# Oscillator_RevB.net
KiCad netlist of a schematic drawn in EAGLE
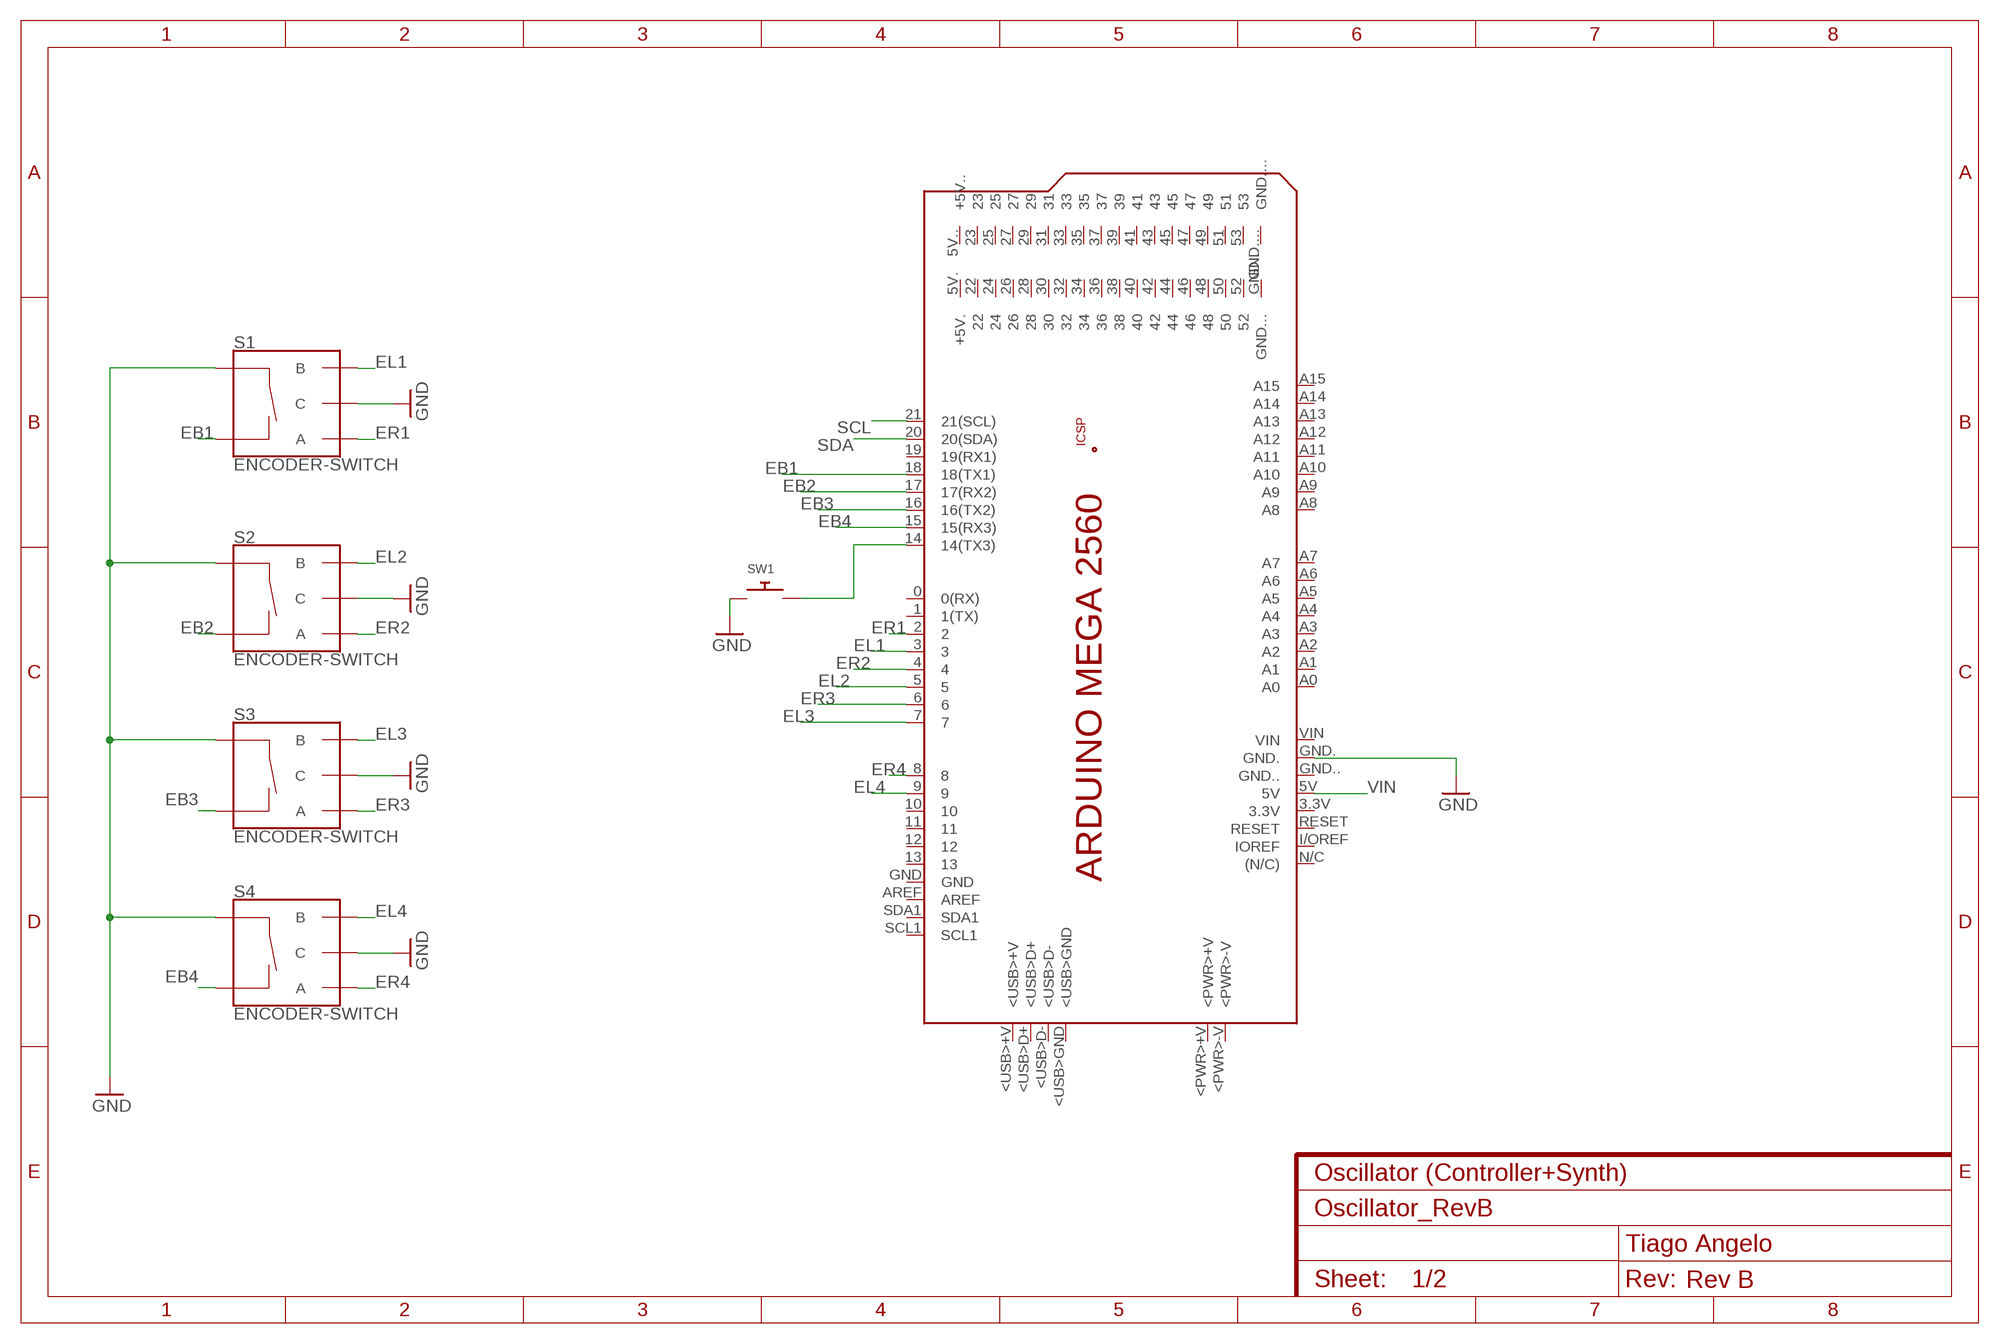
[diagram p0: schematic, sheet 1]
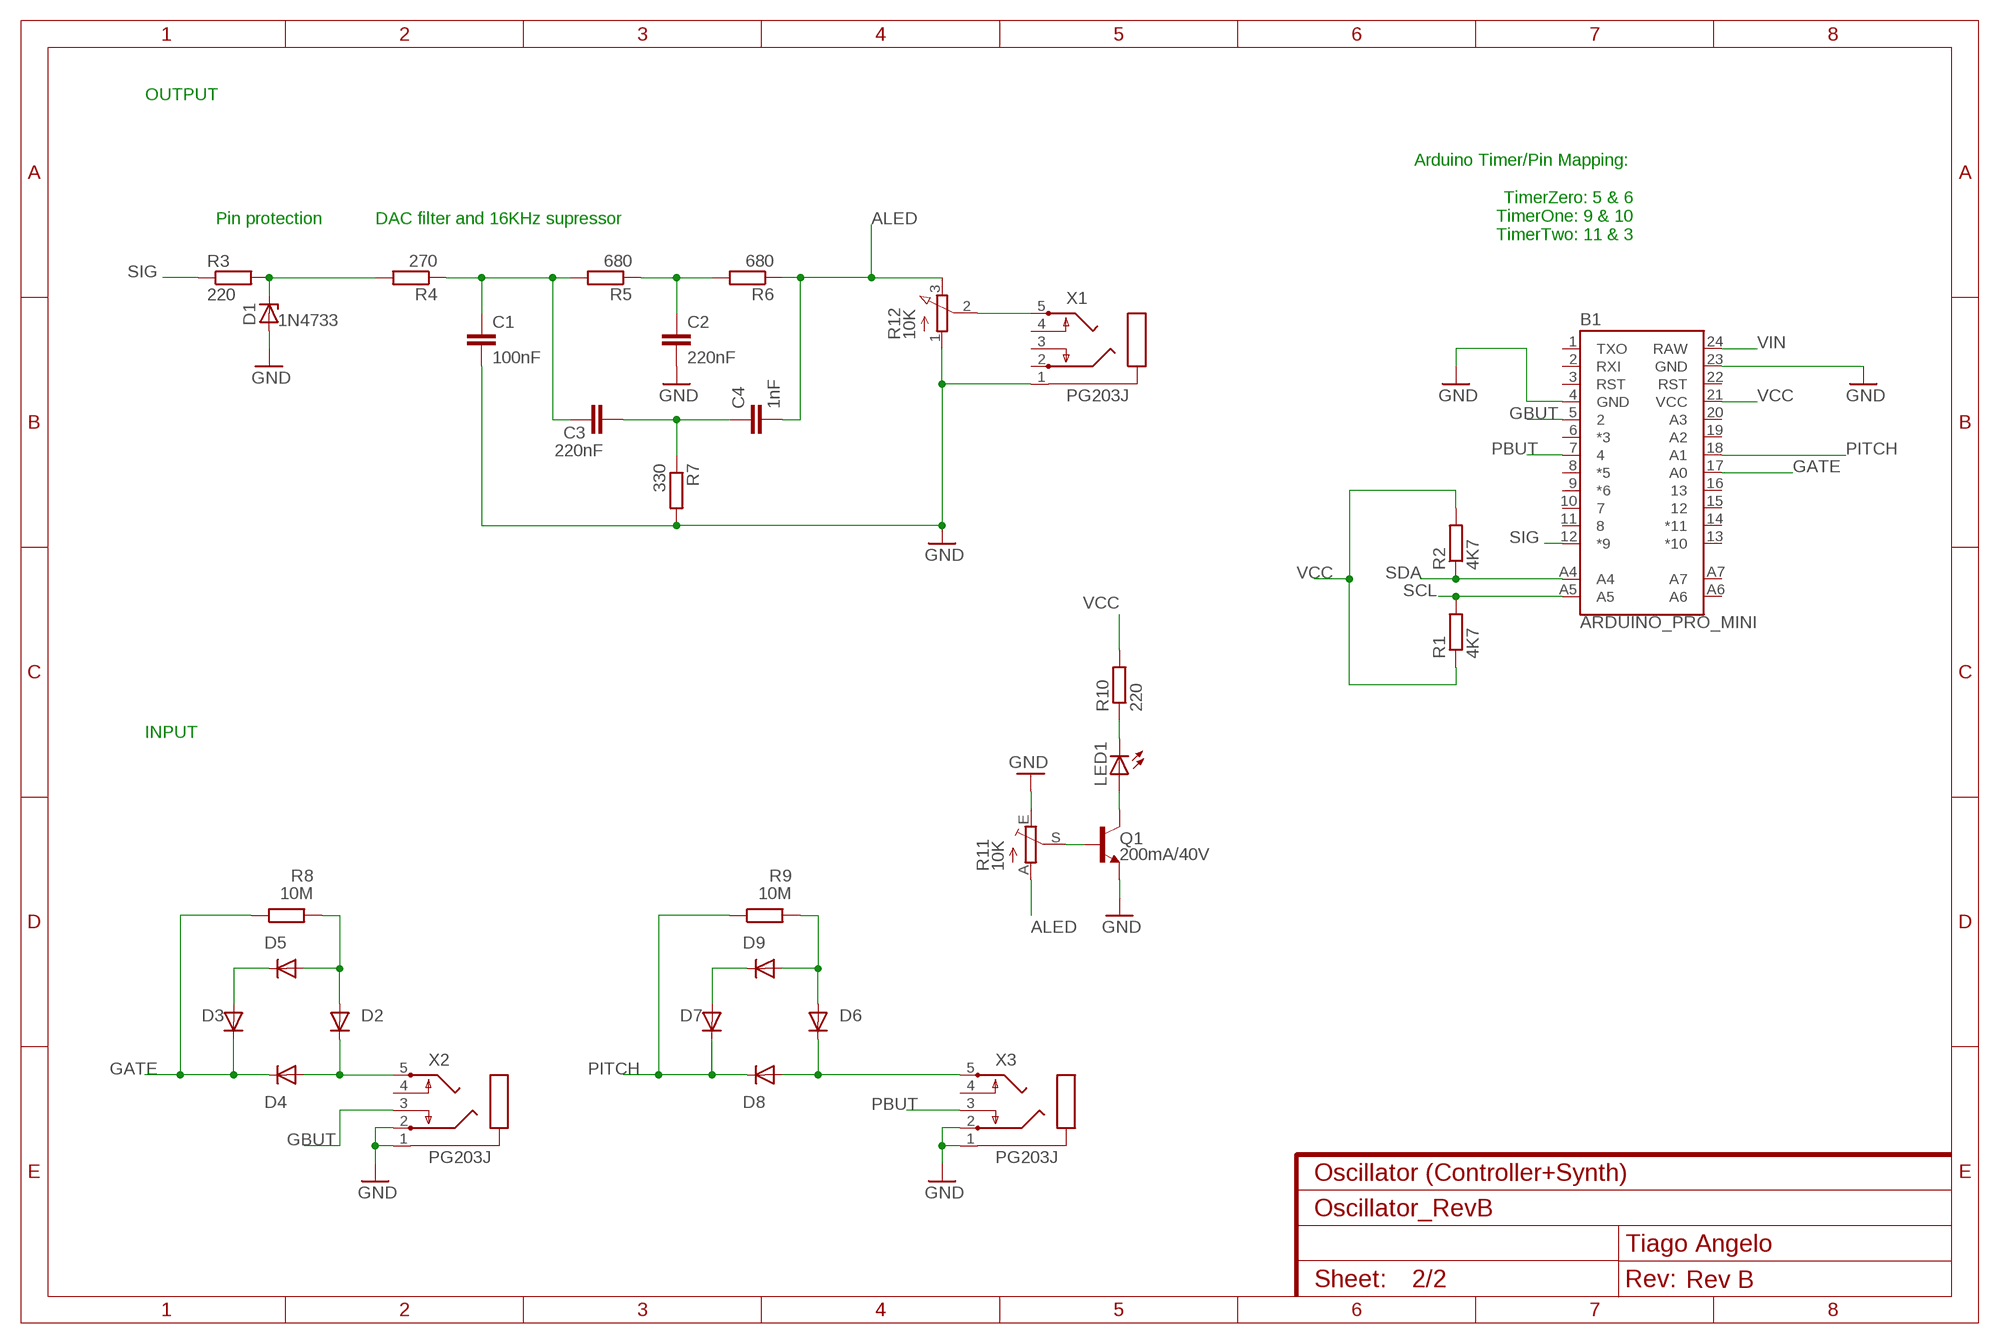
[diagram p1: schematic, sheet 2]

(export (version "E")
  (design (tool "Eeschema 10.0.6"))
  (components
    (comp (ref "B1")
      (value "ARDUINO_PRO_MINI")
      (footprint "eagle-import:ARDUINO_PRO_MINI")
      (libsource (lib "eagle-import") (part "ARDUINO_PRO_MINI"))
    )
    (comp (ref "C1")
      (value "100nF")
      (footprint "eagle-import:C5B3")
      (libsource (lib "eagle-import") (part "C5/3"))
    )
    (comp (ref "C2")
      (value "220nF")
      (footprint "eagle-import:C7.5B6")
      (libsource (lib "eagle-import") (part "C7.5/6"))
    )
    (comp (ref "C3")
      (value "220nF")
      (footprint "eagle-import:C7.5B6")
      (libsource (lib "eagle-import") (part "C7.5/6"))
    )
    (comp (ref "C4")
      (value "1nF")
      (footprint "eagle-import:C5B3")
      (libsource (lib "eagle-import") (part "C5/3"))
    )
    (comp (ref "D1")
      (value "1N4733")
      (footprint "eagle-import:DO34Z7")
      (libsource (lib "eagle-import") (part "ZENER-DIODEDO34-7"))
    )
    (comp (ref "D2")
      (value "1N4004")
      (footprint "eagle-import:DO41-10")
      (libsource (lib "eagle-import") (part "1N4004"))
    )
    (comp (ref "D3")
      (value "1N4004")
      (footprint "eagle-import:DO41-10")
      (libsource (lib "eagle-import") (part "1N4004"))
    )
    (comp (ref "D4")
      (value "1N4004")
      (footprint "eagle-import:DO41-10")
      (libsource (lib "eagle-import") (part "1N4004"))
    )
    (comp (ref "D5")
      (value "1N4004")
      (footprint "eagle-import:DO41-10")
      (libsource (lib "eagle-import") (part "1N4004"))
    )
    (comp (ref "D6")
      (value "1N4004")
      (footprint "eagle-import:DO41-10")
      (libsource (lib "eagle-import") (part "1N4004"))
    )
    (comp (ref "D7")
      (value "1N4004")
      (footprint "eagle-import:DO41-10")
      (libsource (lib "eagle-import") (part "1N4004"))
    )
    (comp (ref "D8")
      (value "1N4004")
      (footprint "eagle-import:DO41-10")
      (libsource (lib "eagle-import") (part "1N4004"))
    )
    (comp (ref "D9")
      (value "1N4004")
      (footprint "eagle-import:DO41-10")
      (libsource (lib "eagle-import") (part "1N4004"))
    )
    (comp (ref "LED1")
      (value "LED5MM")
      (footprint "eagle-import:LED5MM")
      (libsource (lib "eagle-import") (part "LED5MM"))
    )
    (comp (ref "Q1")
      (value "200mA/40V")
      (footprint "eagle-import:TO-92")
      (libsource (lib "eagle-import") (part "TRANS_NPN-2N3904"))
    )
    (comp (ref "R1")
      (value "4K7")
      (footprint "eagle-import:0204_7")
      (libsource (lib "eagle-import") (part "R-EU_0204/7"))
    )
    (comp (ref "R2")
      (value "4K7")
      (footprint "eagle-import:0204_7")
      (libsource (lib "eagle-import") (part "R-EU_0204/7"))
    )
    (comp (ref "R3")
      (value "220")
      (footprint "eagle-import:0204_7")
      (libsource (lib "eagle-import") (part "R-EU_0204/7"))
    )
    (comp (ref "R4")
      (value "270")
      (footprint "eagle-import:0204_7")
      (libsource (lib "eagle-import") (part "R-EU_0204/7"))
    )
    (comp (ref "R5")
      (value "680")
      (footprint "eagle-import:0204_7")
      (libsource (lib "eagle-import") (part "R-EU_0204/7"))
    )
    (comp (ref "R6")
      (value "680")
      (footprint "eagle-import:0204_7")
      (libsource (lib "eagle-import") (part "R-EU_0204/7"))
    )
    (comp (ref "R7")
      (value "330")
      (footprint "eagle-import:0204_7")
      (libsource (lib "eagle-import") (part "R-EU_0204/7"))
    )
    (comp (ref "R8")
      (value "10M")
      (footprint "eagle-import:0204_7")
      (libsource (lib "eagle-import") (part "R-EU_0204/7"))
    )
    (comp (ref "R9")
      (value "10M")
      (footprint "eagle-import:0204_7")
      (libsource (lib "eagle-import") (part "R-EU_0204/7"))
    )
    (comp (ref "R10")
      (value "220")
      (footprint "eagle-import:0204_7")
      (libsource (lib "eagle-import") (part "R-EU_0204/7"))
    )
    (comp (ref "R11")
      (value "10K")
      (footprint "eagle-import:LI10")
      (libsource (lib "eagle-import") (part "TRIM_EU-LI10"))
    )
    (comp (ref "R12")
      (value "10K")
      (footprint "eagle-import:3RP_1610N")
      (libsource (lib "eagle-import") (part "3RP/1610N"))
    )
    (comp (ref "X1")
      (value "PG203J")
      (footprint "eagle-import:PG203J")
      (libsource (lib "eagle-import") (part "PG203J"))
    )
    (comp (ref "X2")
      (value "PG203J")
      (footprint "eagle-import:PG203J")
      (libsource (lib "eagle-import") (part "PG203J"))
    )
    (comp (ref "X3")
      (value "PG203J")
      (footprint "eagle-import:PG203J")
      (libsource (lib "eagle-import") (part "PG203J"))
    )
    (comp (ref "PCB1")
      (value "ARDUINO_MEGA2560")
      (footprint "eagle-import:ARDUINO_MEGA2560")
      (libsource (lib "eagle-import") (part "ARDUINO_MEGA2560"))
    )
    (comp (ref "S1")
      (value "ENCODER-SWITCH")
      (footprint "eagle-import:ROTARY_ENC_PLAIN")
      (libsource (lib "eagle-import") (part "ENCODER-SWITCH"))
    )
    (comp (ref "S2")
      (value "ENCODER-SWITCH")
      (footprint "eagle-import:ROTARY_ENC_PLAIN")
      (libsource (lib "eagle-import") (part "ENCODER-SWITCH"))
    )
    (comp (ref "S3")
      (value "ENCODER-SWITCH")
      (footprint "eagle-import:ROTARY_ENC_PLAIN")
      (libsource (lib "eagle-import") (part "ENCODER-SWITCH"))
    )
    (comp (ref "S4")
      (value "ENCODER-SWITCH")
      (footprint "eagle-import:ROTARY_ENC_PLAIN")
      (libsource (lib "eagle-import") (part "ENCODER-SWITCH"))
    )
    (comp (ref "SW1")
      (value "SWITCH_PUSHBUTTONEVQ-PE")
      (footprint "eagle-import:TACT_PANA-EVQ")
      (libsource (lib "eagle-import") (part "SWITCH_PUSHBUTTONEVQ-PE"))
    )
  )
  (nets
    (net (code "1") (name "ALED") (class "Default")
      (node (ref "C4") (pin "2") (pinfunction "2_2") (pintype "passive"))
      (node (ref "R11") (pin "A") (pinfunction "A_A") (pintype "passive"))
      (node (ref "R12") (pin "3") (pinfunction "E_3") (pintype "passive"))
      (node (ref "R6") (pin "1") (pinfunction "1_1") (pintype "passive"))
    )
    (net (code "2") (name "EB1") (class "Default")
      (node (ref "PCB1") (pin "18") (pinfunction "18(TX1)_18") (pintype "bidirectional"))
      (node (ref "S1") (pin "SW-") (pinfunction "SW-_SW-") (pintype "bidirectional"))
    )
    (net (code "3") (name "EB2") (class "Default")
      (node (ref "PCB1") (pin "17") (pinfunction "17(RX2)_17") (pintype "bidirectional"))
      (node (ref "S2") (pin "SW-") (pinfunction "SW-_SW-") (pintype "bidirectional"))
    )
    (net (code "4") (name "EB3") (class "Default")
      (node (ref "PCB1") (pin "16") (pinfunction "16(TX2)_16") (pintype "bidirectional"))
      (node (ref "S3") (pin "SW-") (pinfunction "SW-_SW-") (pintype "bidirectional"))
    )
    (net (code "5") (name "EB4") (class "Default")
      (node (ref "PCB1") (pin "15") (pinfunction "15(RX3)_15") (pintype "bidirectional"))
      (node (ref "S4") (pin "SW-") (pinfunction "SW-_SW-") (pintype "bidirectional"))
    )
    (net (code "6") (name "EL1") (class "Default")
      (node (ref "PCB1") (pin "3") (pinfunction "3_3") (pintype "bidirectional"))
      (node (ref "S1") (pin "B") (pinfunction "B_B") (pintype "bidirectional"))
    )
    (net (code "7") (name "EL2") (class "Default")
      (node (ref "PCB1") (pin "5") (pinfunction "5_5") (pintype "bidirectional"))
      (node (ref "S2") (pin "B") (pinfunction "B_B") (pintype "bidirectional"))
    )
    (net (code "8") (name "EL3") (class "Default")
      (node (ref "PCB1") (pin "7") (pinfunction "7_7") (pintype "bidirectional"))
      (node (ref "S3") (pin "B") (pinfunction "B_B") (pintype "bidirectional"))
    )
    (net (code "9") (name "EL4") (class "Default")
      (node (ref "PCB1") (pin "9") (pinfunction "9_9") (pintype "bidirectional"))
      (node (ref "S4") (pin "B") (pinfunction "B_B") (pintype "bidirectional"))
    )
    (net (code "10") (name "ER1") (class "Default")
      (node (ref "PCB1") (pin "2") (pinfunction "2_2") (pintype "bidirectional"))
      (node (ref "S1") (pin "A") (pinfunction "A_A") (pintype "bidirectional"))
    )
    (net (code "11") (name "ER2") (class "Default")
      (node (ref "PCB1") (pin "4") (pinfunction "4_4") (pintype "bidirectional"))
      (node (ref "S2") (pin "A") (pinfunction "A_A") (pintype "bidirectional"))
    )
    (net (code "12") (name "ER3") (class "Default")
      (node (ref "PCB1") (pin "6") (pinfunction "6_6") (pintype "bidirectional"))
      (node (ref "S3") (pin "A") (pinfunction "A_A") (pintype "bidirectional"))
    )
    (net (code "13") (name "ER4") (class "Default")
      (node (ref "PCB1") (pin "8") (pinfunction "8_8") (pintype "bidirectional"))
      (node (ref "S4") (pin "A") (pinfunction "A_A") (pintype "bidirectional"))
    )
    (net (code "14") (name "GATE") (class "Default")
      (node (ref "B1") (pin "17") (pinfunction "A0_17") (pintype "bidirectional"))
      (node (ref "D3") (pin "C") (pinfunction "C_C") (pintype "passive"))
      (node (ref "D4") (pin "C") (pinfunction "C_C") (pintype "passive"))
      (node (ref "R8") (pin "1") (pinfunction "1_1") (pintype "passive"))
    )
    (net (code "15") (name "GBUT") (class "Default")
      (node (ref "B1") (pin "5") (pinfunction "2_5") (pintype "bidirectional"))
      (node (ref "X2") (pin "3") (pinfunction "3_3") (pintype "passive"))
    )
    (net (code "16") (name "GND") (class "Default")
      (node (ref "B1") (pin "23") (pinfunction "GND_23") (pintype "power_in"))
      (node (ref "B1") (pin "4") (pinfunction "GND_4") (pintype "power_in"))
      (node (ref "C1") (pin "2") (pinfunction "2_2") (pintype "passive"))
      (node (ref "C2") (pin "2") (pinfunction "2_2") (pintype "passive"))
      (node (ref "D1") (pin "A") (pinfunction "A_A") (pintype "passive"))
      (node (ref "PCB1") (pin "GND.") (pinfunction "GND._GND.") (pintype "bidirectional"))
      (node (ref "Q1") (pin "1") (pinfunction "E_1") (pintype "passive"))
      (node (ref "R11") (pin "E") (pinfunction "E_E") (pintype "passive"))
      (node (ref "R12") (pin "1") (pinfunction "A_1") (pintype "passive"))
      (node (ref "R7") (pin "2") (pinfunction "2_2") (pintype "passive"))
      (node (ref "S1") (pin "C") (pinfunction "C_C") (pintype "bidirectional"))
      (node (ref "S1") (pin "SW+") (pinfunction "SW+_SW+") (pintype "bidirectional"))
      (node (ref "S2") (pin "C") (pinfunction "C_C") (pintype "bidirectional"))
      (node (ref "S2") (pin "SW+") (pinfunction "SW+_SW+") (pintype "bidirectional"))
      (node (ref "S3") (pin "C") (pinfunction "C_C") (pintype "bidirectional"))
      (node (ref "S3") (pin "SW+") (pinfunction "SW+_SW+") (pintype "bidirectional"))
      (node (ref "S4") (pin "C") (pinfunction "C_C") (pintype "bidirectional"))
      (node (ref "S4") (pin "SW+") (pinfunction "SW+_SW+") (pintype "bidirectional"))
      (node (ref "SW1") (pin "P$1") (pinfunction "P$1_P$1") (pintype "passive"))
      (node (ref "X1") (pin "1") (pinfunction "1_1") (pintype "passive"))
      (node (ref "X2") (pin "1") (pinfunction "1_1") (pintype "passive"))
      (node (ref "X2") (pin "2") (pinfunction "2_2") (pintype "passive"))
      (node (ref "X3") (pin "1") (pinfunction "1_1") (pintype "passive"))
      (node (ref "X3") (pin "2") (pinfunction "2_2") (pintype "passive"))
    )
    (net (code "17") (name "Net-(C1-Pad1)") (class "Default")
      (node (ref "C1") (pin "1") (pinfunction "1_1") (pintype "passive"))
      (node (ref "C3") (pin "1") (pinfunction "1_1") (pintype "passive"))
      (node (ref "R4") (pin "1") (pinfunction "1_1") (pintype "passive"))
      (node (ref "R5") (pin "2") (pinfunction "2_2") (pintype "passive"))
    )
    (net (code "18") (name "Net-(C2-Pad1)") (class "Default")
      (node (ref "C2") (pin "1") (pinfunction "1_1") (pintype "passive"))
      (node (ref "R5") (pin "1") (pinfunction "1_1") (pintype "passive"))
      (node (ref "R6") (pin "2") (pinfunction "2_2") (pintype "passive"))
    )
    (net (code "19") (name "Net-(C3-Pad2)") (class "Default")
      (node (ref "C3") (pin "2") (pinfunction "2_2") (pintype "passive"))
      (node (ref "C4") (pin "1") (pinfunction "1_1") (pintype "passive"))
      (node (ref "R7") (pin "1") (pinfunction "1_1") (pintype "passive"))
    )
    (net (code "20") (name "Net-(D1-PadC)") (class "Default")
      (node (ref "D1") (pin "C") (pinfunction "C_C") (pintype "passive"))
      (node (ref "R3") (pin "2") (pinfunction "2_2") (pintype "passive"))
      (node (ref "R4") (pin "2") (pinfunction "2_2") (pintype "passive"))
    )
    (net (code "21") (name "Net-(D2-PadA)") (class "Default")
      (node (ref "D2") (pin "A") (pinfunction "A_A") (pintype "passive"))
      (node (ref "D5") (pin "A") (pinfunction "A_A") (pintype "passive"))
      (node (ref "R8") (pin "2") (pinfunction "2_2") (pintype "passive"))
    )
    (net (code "22") (name "Net-(D2-PadC)") (class "Default")
      (node (ref "D2") (pin "C") (pinfunction "C_C") (pintype "passive"))
      (node (ref "D4") (pin "A") (pinfunction "A_A") (pintype "passive"))
      (node (ref "X2") (pin "5") (pinfunction "5_5") (pintype "passive"))
    )
    (net (code "23") (name "Net-(D3-PadA)") (class "Default")
      (node (ref "D3") (pin "A") (pinfunction "A_A") (pintype "passive"))
      (node (ref "D5") (pin "C") (pinfunction "C_C") (pintype "passive"))
    )
    (net (code "24") (name "Net-(D6-PadA)") (class "Default")
      (node (ref "D6") (pin "A") (pinfunction "A_A") (pintype "passive"))
      (node (ref "D9") (pin "A") (pinfunction "A_A") (pintype "passive"))
      (node (ref "R9") (pin "2") (pinfunction "2_2") (pintype "passive"))
    )
    (net (code "25") (name "Net-(D6-PadC)") (class "Default")
      (node (ref "D6") (pin "C") (pinfunction "C_C") (pintype "passive"))
      (node (ref "D8") (pin "A") (pinfunction "A_A") (pintype "passive"))
      (node (ref "X3") (pin "5") (pinfunction "5_5") (pintype "passive"))
    )
    (net (code "26") (name "Net-(D7-PadA)") (class "Default")
      (node (ref "D7") (pin "A") (pinfunction "A_A") (pintype "passive"))
      (node (ref "D9") (pin "C") (pinfunction "C_C") (pintype "passive"))
    )
    (net (code "27") (name "Net-(LED1-C)") (class "Default")
      (node (ref "LED1") (pin "K") (pinfunction "C_K") (pintype "passive"))
      (node (ref "R10") (pin "1") (pinfunction "1_1") (pintype "passive"))
    )
    (net (code "28") (name "Net-(PCB1-14(TX3))") (class "Default")
      (node (ref "PCB1") (pin "14") (pinfunction "14(TX3)_14") (pintype "bidirectional"))
      (node (ref "SW1") (pin "P$2") (pinfunction "P$2_P$2") (pintype "passive"))
    )
    (net (code "29") (name "Net-(Q1-B)") (class "Default")
      (node (ref "Q1") (pin "2") (pinfunction "B_2") (pintype "passive"))
      (node (ref "R11") (pin "S") (pinfunction "S_S") (pintype "passive"))
    )
    (net (code "30") (name "Net-(Q1-C)") (class "Default")
      (node (ref "LED1") (pin "A") (pinfunction "A_A") (pintype "passive"))
      (node (ref "Q1") (pin "3") (pinfunction "C_3") (pintype "passive"))
    )
    (net (code "31") (name "Net-(R12-S)") (class "Default")
      (node (ref "R12") (pin "2") (pinfunction "S_2") (pintype "passive"))
      (node (ref "X1") (pin "5") (pinfunction "5_5") (pintype "passive"))
    )
    (net (code "32") (name "PBUT") (class "Default")
      (node (ref "B1") (pin "7") (pinfunction "4_7") (pintype "bidirectional"))
      (node (ref "X3") (pin "3") (pinfunction "3_3") (pintype "passive"))
    )
    (net (code "33") (name "PITCH") (class "Default")
      (node (ref "B1") (pin "18") (pinfunction "A1_18") (pintype "bidirectional"))
      (node (ref "D7") (pin "C") (pinfunction "C_C") (pintype "passive"))
      (node (ref "D8") (pin "C") (pinfunction "C_C") (pintype "passive"))
      (node (ref "R9") (pin "1") (pinfunction "1_1") (pintype "passive"))
    )
    (net (code "34") (name "SCL") (class "Default")
      (node (ref "B1") (pin "A5") (pinfunction "A5_A5") (pintype "bidirectional"))
      (node (ref "PCB1") (pin "21") (pinfunction "21(SCL)_21") (pintype "bidirectional"))
      (node (ref "R1") (pin "2") (pinfunction "2_2") (pintype "passive"))
    )
    (net (code "35") (name "SDA") (class "Default")
      (node (ref "B1") (pin "A4") (pinfunction "A4_A4") (pintype "bidirectional"))
      (node (ref "PCB1") (pin "20") (pinfunction "20(SDA)_20") (pintype "bidirectional"))
      (node (ref "R2") (pin "1") (pinfunction "1_1") (pintype "passive"))
    )
    (net (code "36") (name "SIG") (class "Default")
      (node (ref "B1") (pin "12") (pinfunction "*9_12") (pintype "bidirectional"))
      (node (ref "R3") (pin "1") (pinfunction "1_1") (pintype "passive"))
    )
    (net (code "37") (name "VCC") (class "Default")
      (node (ref "B1") (pin "21") (pinfunction "VCC_21") (pintype "power_in"))
      (node (ref "R1") (pin "1") (pinfunction "1_1") (pintype "passive"))
      (node (ref "R10") (pin "2") (pinfunction "2_2") (pintype "passive"))
      (node (ref "R2") (pin "2") (pinfunction "2_2") (pintype "passive"))
    )
    (net (code "38") (name "VIN") (class "Default")
      (node (ref "B1") (pin "24") (pinfunction "RAW_24") (pintype "power_in"))
      (node (ref "PCB1") (pin "5V") (pinfunction "5V_5V") (pintype "bidirectional"))
    )
    (net (code "39") (name "unconnected-(B1-*3-Pad6)") (class "Default")
      (node (ref "B1") (pin "6") (pinfunction "*3_6") (pintype "bidirectional"))
    )
    (net (code "40") (name "unconnected-(B1-*5-Pad8)") (class "Default")
      (node (ref "B1") (pin "8") (pinfunction "*5_8") (pintype "bidirectional"))
    )
    (net (code "41") (name "unconnected-(B1-*6-Pad9)") (class "Default")
      (node (ref "B1") (pin "9") (pinfunction "*6_9") (pintype "bidirectional"))
    )
    (net (code "42") (name "unconnected-(B1-*10-Pad13)") (class "Default")
      (node (ref "B1") (pin "13") (pinfunction "*10_13") (pintype "bidirectional"))
    )
    (net (code "43") (name "unconnected-(B1-*11-Pad14)") (class "Default")
      (node (ref "B1") (pin "14") (pinfunction "*11_14") (pintype "bidirectional"))
    )
    (net (code "44") (name "unconnected-(B1-7-Pad10)") (class "Default")
      (node (ref "B1") (pin "10") (pinfunction "7_10") (pintype "bidirectional"))
    )
    (net (code "45") (name "unconnected-(B1-8-Pad11)") (class "Default")
      (node (ref "B1") (pin "11") (pinfunction "8_11") (pintype "bidirectional"))
    )
    (net (code "46") (name "unconnected-(B1-12-Pad15)") (class "Default")
      (node (ref "B1") (pin "15") (pinfunction "12_15") (pintype "bidirectional"))
    )
    (net (code "47") (name "unconnected-(B1-13-Pad16)") (class "Default")
      (node (ref "B1") (pin "16") (pinfunction "13_16") (pintype "bidirectional"))
    )
    (net (code "48") (name "unconnected-(B1-A2-Pad19)") (class "Default")
      (node (ref "B1") (pin "19") (pinfunction "A2_19") (pintype "bidirectional"))
    )
    (net (code "49") (name "unconnected-(B1-A3-Pad20)") (class "Default")
      (node (ref "B1") (pin "20") (pinfunction "A3_20") (pintype "bidirectional"))
    )
    (net (code "50") (name "unconnected-(B1-PadA6)") (class "Default")
      (node (ref "B1") (pin "A6") (pinfunction "A6_A6") (pintype "bidirectional"))
    )
    (net (code "51") (name "unconnected-(B1-PadA7)") (class "Default")
      (node (ref "B1") (pin "A7") (pinfunction "A7_A7") (pintype "bidirectional"))
    )
    (net (code "52") (name "unconnected-(B1-RST-Pad3)") (class "Default")
      (node (ref "B1") (pin "3") (pinfunction "RST_3") (pintype "bidirectional"))
    )
    (net (code "53") (name "unconnected-(B1-RST-Pad22)") (class "Default")
      (node (ref "B1") (pin "22") (pinfunction "RST_22") (pintype "bidirectional"))
    )
    (net (code "54") (name "unconnected-(B1-RXI-Pad2)") (class "Default")
      (node (ref "B1") (pin "2") (pinfunction "RXI_2") (pintype "bidirectional"))
    )
    (net (code "55") (name "unconnected-(B1-TXO-Pad1)") (class "Default")
      (node (ref "B1") (pin "1") (pinfunction "TXO_1") (pintype "bidirectional"))
    )
    (net (code "56") (name "unconnected-(PCB1-(N{slash}C)-PadN{slash}C)") (class "Default")
      (node (ref "PCB1") (pin "N/C") (pinfunction "(N/C)_N/C") (pintype "bidirectional"))
    )
    (net (code "57") (name "unconnected-(PCB1-+5V.-Pad5V.)") (class "Default")
      (node (ref "PCB1") (pin "5V.") (pinfunction "+5V._5V.") (pintype "bidirectional"))
    )
    (net (code "58") (name "unconnected-(PCB1-+5V..-Pad5V..)") (class "Default")
      (node (ref "PCB1") (pin "5V..") (pinfunction "+5V.._5V..") (pintype "bidirectional"))
    )
    (net (code "59") (name "unconnected-(PCB1-0(RX)-Pad0)") (class "Default")
      (node (ref "PCB1") (pin "0") (pinfunction "0(RX)_0") (pintype "bidirectional"))
    )
    (net (code "60") (name "unconnected-(PCB1-1(TX)-Pad1)") (class "Default")
      (node (ref "PCB1") (pin "1") (pinfunction "1(TX)_1") (pintype "bidirectional"))
    )
    (net (code "61") (name "unconnected-(PCB1-19(RX1)-Pad19)") (class "Default")
      (node (ref "PCB1") (pin "19") (pinfunction "19(RX1)_19") (pintype "bidirectional"))
    )
    (net (code "62") (name "unconnected-(PCB1-IOREF-PadI{slash}OREF)") (class "Default")
      (node (ref "PCB1") (pin "I/OREF") (pinfunction "IOREF_I/OREF") (pintype "bidirectional"))
    )
    (net (code "63") (name "unconnected-(PCB1-Pad+5V_)") (class "Default")
      (node (ref "PCB1") (pin "+5V_") (pinfunction "+5V__+5V_") (pintype "bidirectional"))
    )
    (net (code "64") (name "unconnected-(PCB1-Pad3.3V)") (class "Default")
      (node (ref "PCB1") (pin "3.3V") (pinfunction "3.3V_3.3V") (pintype "bidirectional"))
    )
    (net (code "65") (name "unconnected-(PCB1-Pad10)") (class "Default")
      (node (ref "PCB1") (pin "10") (pinfunction "10_10") (pintype "bidirectional"))
    )
    (net (code "66") (name "unconnected-(PCB1-Pad11)") (class "Default")
      (node (ref "PCB1") (pin "11") (pinfunction "11_11") (pintype "bidirectional"))
    )
    (net (code "67") (name "unconnected-(PCB1-Pad12)") (class "Default")
      (node (ref "PCB1") (pin "12") (pinfunction "12_12") (pintype "bidirectional"))
    )
    (net (code "68") (name "unconnected-(PCB1-Pad13)") (class "Default")
      (node (ref "PCB1") (pin "13") (pinfunction "13_13") (pintype "bidirectional"))
    )
    (net (code "69") (name "unconnected-(PCB1-Pad22)") (class "Default")
      (node (ref "PCB1") (pin "22") (pinfunction "22_22") (pintype "bidirectional"))
    )
    (net (code "70") (name "unconnected-(PCB1-Pad23)") (class "Default")
      (node (ref "PCB1") (pin "23") (pinfunction "23_23") (pintype "bidirectional"))
    )
    (net (code "71") (name "unconnected-(PCB1-Pad24)") (class "Default")
      (node (ref "PCB1") (pin "24") (pinfunction "24_24") (pintype "bidirectional"))
    )
    (net (code "72") (name "unconnected-(PCB1-Pad25)") (class "Default")
      (node (ref "PCB1") (pin "25") (pinfunction "25_25") (pintype "bidirectional"))
    )
    (net (code "73") (name "unconnected-(PCB1-Pad26)") (class "Default")
      (node (ref "PCB1") (pin "26") (pinfunction "26_26") (pintype "bidirectional"))
    )
    (net (code "74") (name "unconnected-(PCB1-Pad27)") (class "Default")
      (node (ref "PCB1") (pin "27") (pinfunction "27_27") (pintype "bidirectional"))
    )
    (net (code "75") (name "unconnected-(PCB1-Pad28)") (class "Default")
      (node (ref "PCB1") (pin "28") (pinfunction "28_28") (pintype "bidirectional"))
    )
    (net (code "76") (name "unconnected-(PCB1-Pad29)") (class "Default")
      (node (ref "PCB1") (pin "29") (pinfunction "29_29") (pintype "bidirectional"))
    )
    (net (code "77") (name "unconnected-(PCB1-Pad30)") (class "Default")
      (node (ref "PCB1") (pin "30") (pinfunction "30_30") (pintype "bidirectional"))
    )
    (net (code "78") (name "unconnected-(PCB1-Pad31)") (class "Default")
      (node (ref "PCB1") (pin "31") (pinfunction "31_31") (pintype "bidirectional"))
    )
    (net (code "79") (name "unconnected-(PCB1-Pad32)") (class "Default")
      (node (ref "PCB1") (pin "32") (pinfunction "32_32") (pintype "bidirectional"))
    )
    (net (code "80") (name "unconnected-(PCB1-Pad33)") (class "Default")
      (node (ref "PCB1") (pin "33") (pinfunction "33_33") (pintype "bidirectional"))
    )
    (net (code "81") (name "unconnected-(PCB1-Pad34)") (class "Default")
      (node (ref "PCB1") (pin "34") (pinfunction "34_34") (pintype "bidirectional"))
    )
    (net (code "82") (name "unconnected-(PCB1-Pad35)") (class "Default")
      (node (ref "PCB1") (pin "35") (pinfunction "35_35") (pintype "bidirectional"))
    )
    (net (code "83") (name "unconnected-(PCB1-Pad36)") (class "Default")
      (node (ref "PCB1") (pin "36") (pinfunction "36_36") (pintype "bidirectional"))
    )
    (net (code "84") (name "unconnected-(PCB1-Pad37)") (class "Default")
      (node (ref "PCB1") (pin "37") (pinfunction "37_37") (pintype "bidirectional"))
    )
    (net (code "85") (name "unconnected-(PCB1-Pad38)") (class "Default")
      (node (ref "PCB1") (pin "38") (pinfunction "38_38") (pintype "bidirectional"))
    )
    (net (code "86") (name "unconnected-(PCB1-Pad39)") (class "Default")
      (node (ref "PCB1") (pin "39") (pinfunction "39_39") (pintype "bidirectional"))
    )
    (net (code "87") (name "unconnected-(PCB1-Pad40)") (class "Default")
      (node (ref "PCB1") (pin "40") (pinfunction "40_40") (pintype "bidirectional"))
    )
    (net (code "88") (name "unconnected-(PCB1-Pad41)") (class "Default")
      (node (ref "PCB1") (pin "41") (pinfunction "41_41") (pintype "bidirectional"))
    )
    (net (code "89") (name "unconnected-(PCB1-Pad42)") (class "Default")
      (node (ref "PCB1") (pin "42") (pinfunction "42_42") (pintype "bidirectional"))
    )
    (net (code "90") (name "unconnected-(PCB1-Pad43)") (class "Default")
      (node (ref "PCB1") (pin "43") (pinfunction "43_43") (pintype "bidirectional"))
    )
    (net (code "91") (name "unconnected-(PCB1-Pad44)") (class "Default")
      (node (ref "PCB1") (pin "44") (pinfunction "44_44") (pintype "bidirectional"))
    )
    (net (code "92") (name "unconnected-(PCB1-Pad45)") (class "Default")
      (node (ref "PCB1") (pin "45") (pinfunction "45_45") (pintype "bidirectional"))
    )
    (net (code "93") (name "unconnected-(PCB1-Pad46)") (class "Default")
      (node (ref "PCB1") (pin "46") (pinfunction "46_46") (pintype "bidirectional"))
    )
    (net (code "94") (name "unconnected-(PCB1-Pad47)") (class "Default")
      (node (ref "PCB1") (pin "47") (pinfunction "47_47") (pintype "bidirectional"))
    )
    (net (code "95") (name "unconnected-(PCB1-Pad48)") (class "Default")
      (node (ref "PCB1") (pin "48") (pinfunction "48_48") (pintype "bidirectional"))
    )
    (net (code "96") (name "unconnected-(PCB1-Pad49)") (class "Default")
      (node (ref "PCB1") (pin "49") (pinfunction "49_49") (pintype "bidirectional"))
    )
    (net (code "97") (name "unconnected-(PCB1-Pad50)") (class "Default")
      (node (ref "PCB1") (pin "50") (pinfunction "50_50") (pintype "bidirectional"))
    )
    (net (code "98") (name "unconnected-(PCB1-Pad51)") (class "Default")
      (node (ref "PCB1") (pin "51") (pinfunction "51_51") (pintype "bidirectional"))
    )
    (net (code "99") (name "unconnected-(PCB1-Pad52)") (class "Default")
      (node (ref "PCB1") (pin "52") (pinfunction "52_52") (pintype "bidirectional"))
    )
    (net (code "100") (name "unconnected-(PCB1-Pad53)") (class "Default")
      (node (ref "PCB1") (pin "53") (pinfunction "53_53") (pintype "bidirectional"))
    )
    (net (code "101") (name "unconnected-(PCB1-Pad<PWR>+V)") (class "Default")
      (node (ref "PCB1") (pin "<PWR>+V") (pinfunction "<PWR>+V_<PWR>+V") (pintype "no_connect"))
    )
    (net (code "102") (name "unconnected-(PCB1-Pad<PWR>-V)") (class "Default")
      (node (ref "PCB1") (pin "<PWR>-V") (pinfunction "<PWR>-V_<PWR>-V") (pintype "no_connect"))
    )
    (net (code "103") (name "unconnected-(PCB1-Pad<USB>+V)") (class "Default")
      (node (ref "PCB1") (pin "<USB>+V") (pinfunction "<USB>+V_<USB>+V") (pintype "no_connect"))
    )
    (net (code "104") (name "unconnected-(PCB1-Pad<USB>D+)") (class "Default")
      (node (ref "PCB1") (pin "<USB>D+") (pinfunction "<USB>D+_<USB>D+") (pintype "no_connect"))
    )
    (net (code "105") (name "unconnected-(PCB1-Pad<USB>D-)") (class "Default")
      (node (ref "PCB1") (pin "<USB>D-") (pinfunction "<USB>D-_<USB>D-") (pintype "no_connect"))
    )
    (net (code "106") (name "unconnected-(PCB1-Pad<USB>GND)") (class "Default")
      (node (ref "PCB1") (pin "<USB>GND") (pinfunction "<USB>GND_<USB>GND") (pintype "no_connect"))
    )
    (net (code "107") (name "unconnected-(PCB1-PadA0)") (class "Default")
      (node (ref "PCB1") (pin "A0") (pinfunction "A0_A0") (pintype "bidirectional"))
    )
    (net (code "108") (name "unconnected-(PCB1-PadA1)") (class "Default")
      (node (ref "PCB1") (pin "A1") (pinfunction "A1_A1") (pintype "bidirectional"))
    )
    (net (code "109") (name "unconnected-(PCB1-PadA2)") (class "Default")
      (node (ref "PCB1") (pin "A2") (pinfunction "A2_A2") (pintype "bidirectional"))
    )
    (net (code "110") (name "unconnected-(PCB1-PadA3)") (class "Default")
      (node (ref "PCB1") (pin "A3") (pinfunction "A3_A3") (pintype "bidirectional"))
    )
    (net (code "111") (name "unconnected-(PCB1-PadA4)") (class "Default")
      (node (ref "PCB1") (pin "A4") (pinfunction "A4_A4") (pintype "bidirectional"))
    )
    (net (code "112") (name "unconnected-(PCB1-PadA5)") (class "Default")
      (node (ref "PCB1") (pin "A5") (pinfunction "A5_A5") (pintype "bidirectional"))
    )
    (net (code "113") (name "unconnected-(PCB1-PadA6)") (class "Default")
      (node (ref "PCB1") (pin "A6") (pinfunction "A6_A6") (pintype "bidirectional"))
    )
    (net (code "114") (name "unconnected-(PCB1-PadA7)") (class "Default")
      (node (ref "PCB1") (pin "A7") (pinfunction "A7_A7") (pintype "bidirectional"))
    )
    (net (code "115") (name "unconnected-(PCB1-PadA8)") (class "Default")
      (node (ref "PCB1") (pin "A8") (pinfunction "A8_A8") (pintype "bidirectional"))
    )
    (net (code "116") (name "unconnected-(PCB1-PadA9)") (class "Default")
      (node (ref "PCB1") (pin "A9") (pinfunction "A9_A9") (pintype "bidirectional"))
    )
    (net (code "117") (name "unconnected-(PCB1-PadA10)") (class "Default")
      (node (ref "PCB1") (pin "A10") (pinfunction "A10_A10") (pintype "bidirectional"))
    )
    (net (code "118") (name "unconnected-(PCB1-PadA11)") (class "Default")
      (node (ref "PCB1") (pin "A11") (pinfunction "A11_A11") (pintype "bidirectional"))
    )
    (net (code "119") (name "unconnected-(PCB1-PadA12)") (class "Default")
      (node (ref "PCB1") (pin "A12") (pinfunction "A12_A12") (pintype "bidirectional"))
    )
    (net (code "120") (name "unconnected-(PCB1-PadA13)") (class "Default")
      (node (ref "PCB1") (pin "A13") (pinfunction "A13_A13") (pintype "bidirectional"))
    )
    (net (code "121") (name "unconnected-(PCB1-PadA14)") (class "Default")
      (node (ref "PCB1") (pin "A14") (pinfunction "A14_A14") (pintype "bidirectional"))
    )
    (net (code "122") (name "unconnected-(PCB1-PadA15)") (class "Default")
      (node (ref "PCB1") (pin "A15") (pinfunction "A15_A15") (pintype "bidirectional"))
    )
    (net (code "123") (name "unconnected-(PCB1-PadAREF)") (class "Default")
      (node (ref "PCB1") (pin "AREF") (pinfunction "AREF_AREF") (pintype "bidirectional"))
    )
    (net (code "124") (name "unconnected-(PCB1-PadGND)") (class "Default")
      (node (ref "PCB1") (pin "GND") (pinfunction "GND_GND") (pintype "bidirectional"))
    )
    (net (code "125") (name "unconnected-(PCB1-PadGND..)") (class "Default")
      (node (ref "PCB1") (pin "GND..") (pinfunction "GND.._GND..") (pintype "bidirectional"))
    )
    (net (code "126") (name "unconnected-(PCB1-PadGND...)") (class "Default")
      (node (ref "PCB1") (pin "GND...") (pinfunction "GND..._GND...") (pintype "bidirectional"))
    )
    (net (code "127") (name "unconnected-(PCB1-PadGND....)") (class "Default")
      (node (ref "PCB1") (pin "GND....") (pinfunction "GND...._GND....") (pintype "bidirectional"))
    )
    (net (code "128") (name "unconnected-(PCB1-PadGND__)") (class "Default")
      (node (ref "PCB1") (pin "GND__") (pinfunction "GND___GND__") (pintype "bidirectional"))
    )
    (net (code "129") (name "unconnected-(PCB1-PadMISO)") (class "Default")
      (node (ref "PCB1") (pin "MISO") (pinfunction "MISO_MISO") (pintype "bidirectional"))
    )
    (net (code "130") (name "unconnected-(PCB1-PadMOSI)") (class "Default")
      (node (ref "PCB1") (pin "MOSI") (pinfunction "MOSI_MOSI") (pintype "bidirectional"))
    )
    (net (code "131") (name "unconnected-(PCB1-PadRESET)") (class "Default")
      (node (ref "PCB1") (pin "RESET") (pinfunction "RESET_RESET") (pintype "bidirectional"))
    )
    (net (code "132") (name "unconnected-(PCB1-PadRESET.)") (class "Default")
      (node (ref "PCB1") (pin "RESET.") (pinfunction "RESET._RESET.") (pintype "bidirectional"))
    )
    (net (code "133") (name "unconnected-(PCB1-PadSCK)") (class "Default")
      (node (ref "PCB1") (pin "SCK") (pinfunction "SCK_SCK") (pintype "bidirectional"))
    )
    (net (code "134") (name "unconnected-(PCB1-PadSCL1)") (class "Default")
      (node (ref "PCB1") (pin "SCL1") (pinfunction "SCL1_SCL1") (pintype "bidirectional"))
    )
    (net (code "135") (name "unconnected-(PCB1-PadSDA1)") (class "Default")
      (node (ref "PCB1") (pin "SDA1") (pinfunction "SDA1_SDA1") (pintype "bidirectional"))
    )
    (net (code "136") (name "unconnected-(PCB1-PadVIN)") (class "Default")
      (node (ref "PCB1") (pin "VIN") (pinfunction "VIN_VIN") (pintype "bidirectional"))
    )
    (net (code "137") (name "unconnected-(X1-Pad2)") (class "Default")
      (node (ref "X1") (pin "2") (pinfunction "2_2") (pintype "passive"))
    )
    (net (code "138") (name "unconnected-(X1-Pad3)") (class "Default")
      (node (ref "X1") (pin "3") (pinfunction "3_3") (pintype "passive"))
    )
    (net (code "139") (name "unconnected-(X1-Pad4)") (class "Default")
      (node (ref "X1") (pin "4") (pinfunction "4_4") (pintype "passive"))
    )
    (net (code "140") (name "unconnected-(X2-Pad4)") (class "Default")
      (node (ref "X2") (pin "4") (pinfunction "4_4") (pintype "passive"))
    )
    (net (code "141") (name "unconnected-(X3-Pad4)") (class "Default")
      (node (ref "X3") (pin "4") (pinfunction "4_4") (pintype "passive"))
    )
  )
)
